# pineapple_2_2013_model_0.net
KiCad netlist of a schematic drawn in EAGLE
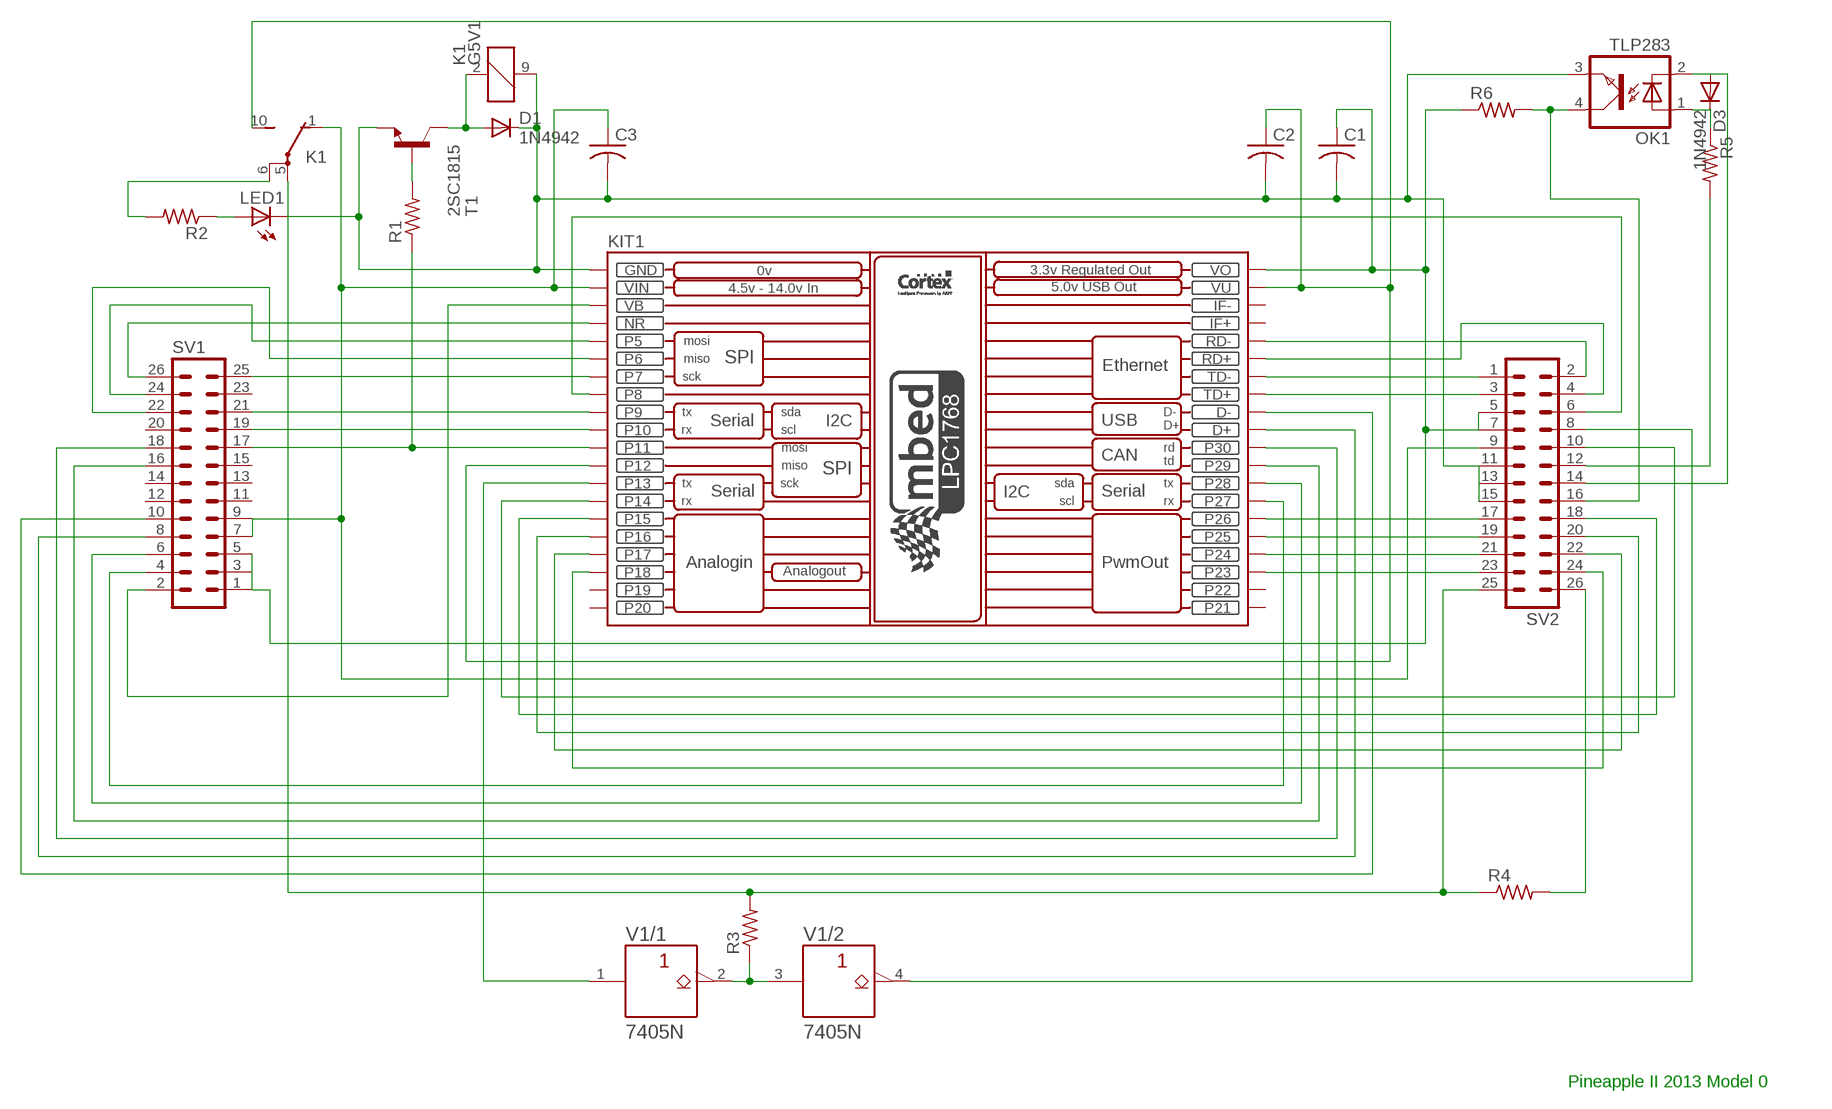
[diagram p0: schematic, sheet 1]

(export (version "E")
  (design (tool "Eeschema 10.0.6"))
  (components
    (comp (ref "C1")
      (value "C-US025-024X044")
      (footprint "eagle-import:C025-024X044")
      (libsource (lib "eagle-import") (part "C-US025-024X044"))
    )
    (comp (ref "C2")
      (value "C-US025-024X044")
      (footprint "eagle-import:C025-024X044")
      (libsource (lib "eagle-import") (part "C-US025-024X044"))
    )
    (comp (ref "C3")
      (value "C-US050-024X044")
      (footprint "eagle-import:C050-024X044")
      (libsource (lib "eagle-import") (part "C-US050-024X044"))
    )
    (comp (ref "D1")
      (value "1N4942")
      (footprint "eagle-import:DO41-10")
      (libsource (lib "eagle-import") (part "1N4942"))
    )
    (comp (ref "D3")
      (value "1N4942")
      (footprint "eagle-import:DO41-10")
      (libsource (lib "eagle-import") (part "1N4942"))
    )
    (comp (ref "K1")
      (value "G5V1")
      (footprint "eagle-import:G5V1")
      (fields (field (name "MPN") "G5V-1-DC24"))
      (libsource (lib "eagle-import") (part "G5V1"))
    )
    (comp (ref "KIT1")
      (value "MBED_NXP_LPC1768")
      (footprint "eagle-import:MBED-KIT")
      (libsource (lib "eagle-import") (part "MBED_NXP_LPC1768"))
    )
    (comp (ref "LED1")
      (value "LED3MM")
      (footprint "eagle-import:LED3MM")
      (libsource (lib "eagle-import") (part "LED3MM"))
    )
    (comp (ref "OK1")
      (value "TLP283")
      (footprint "eagle-import:MINI-FLAT-4")
      (libsource (lib "eagle-import") (part "TLP283"))
    )
    (comp (ref "R1")
      (value "R-US_0204/5")
      (footprint "eagle-import:0204_5")
      (libsource (lib "eagle-import") (part "R-US_0204/5"))
    )
    (comp (ref "R2")
      (value "R-US_0204/5")
      (footprint "eagle-import:0204_5")
      (libsource (lib "eagle-import") (part "R-US_0204/5"))
    )
    (comp (ref "R3")
      (value "R-US_0204/5")
      (footprint "eagle-import:0204_5")
      (libsource (lib "eagle-import") (part "R-US_0204/5"))
    )
    (comp (ref "R4")
      (value "R-US_0204/5")
      (footprint "eagle-import:0204_5")
      (libsource (lib "eagle-import") (part "R-US_0204/5"))
    )
    (comp (ref "R5")
      (value "R-US_0204/5")
      (footprint "eagle-import:0204_5")
      (libsource (lib "eagle-import") (part "R-US_0204/5"))
    )
    (comp (ref "R6")
      (value "R-US_0204/5")
      (footprint "eagle-import:0204_5")
      (libsource (lib "eagle-import") (part "R-US_0204/5"))
    )
    (comp (ref "SV1")
      (value "ML26L")
      (footprint "eagle-import:ML26L")
      (libsource (lib "eagle-import") (part "ML26L"))
    )
    (comp (ref "SV2")
      (value "ML26L")
      (footprint "eagle-import:ML26L")
      (libsource (lib "eagle-import") (part "ML26L"))
    )
    (comp (ref "T1")
      (value "2SC1815")
      (footprint "eagle-import:TO92-ECB")
      (libsource (lib "eagle-import") (part "2SC1815"))
    )
    (comp (ref "V1")
      (value "7405N")
      (footprint "eagle-import:DIL14")
      (libsource (lib "eagle-import") (part "7405N"))
    )
  )
  (nets
    (net (code "1") (name "Net-(K1A-1)") (class "Default")
      (node (ref "D1") (pin "A") (pinfunction "A_A") (pintype "passive"))
      (node (ref "K1") (pin "2") (pinfunction "1_2") (pintype "passive"))
      (node (ref "T1") (pin "C") (pinfunction "C_C") (pintype "passive"))
    )
    (net (code "2") (name "Net-(K1A-2)") (class "Default")
      (node (ref "C1") (pin "2") (pinfunction "2_2") (pintype "passive"))
      (node (ref "C2") (pin "2") (pinfunction "2_2") (pintype "passive"))
      (node (ref "C3") (pin "2") (pinfunction "2_2") (pintype "passive"))
      (node (ref "D1") (pin "C") (pinfunction "C_C") (pintype "passive"))
      (node (ref "K1") (pin "9") (pinfunction "2_9") (pintype "passive"))
      (node (ref "KIT1") (pin "GND") (pinfunction "GND_GND") (pintype "power_in"))
      (node (ref "LED1") (pin "K") (pinfunction "C_K") (pintype "passive"))
      (node (ref "OK1") (pin "3") (pinfunction "EMIT_3") (pintype "passive"))
      (node (ref "SV2") (pin "11") (pinfunction "11_11") (pintype "passive"))
      (node (ref "SV2") (pin "13") (pinfunction "13_13") (pintype "passive"))
      (node (ref "SV2") (pin "15") (pinfunction "15_15") (pintype "passive"))
      (node (ref "T1") (pin "E") (pinfunction "E_E") (pintype "passive"))
    )
    (net (code "3") (name "Net-(K1B-O)") (class "Default")
      (node (ref "C3") (pin "1") (pinfunction "1_1") (pintype "passive"))
      (node (ref "K1") (pin "1") (pinfunction "O_1") (pintype "passive"))
      (node (ref "KIT1") (pin "VIN") (pinfunction "VIN_VIN") (pintype "power_in"))
      (node (ref "SV1") (pin "7") (pinfunction "7_7") (pintype "passive"))
      (node (ref "SV1") (pin "9") (pinfunction "9_9") (pintype "passive"))
      (node (ref "SV2") (pin "9") (pinfunction "9_9") (pintype "passive"))
    )
    (net (code "4") (name "Net-(K1B-P-Pad5)") (class "Default")
      (node (ref "K1") (pin "5") (pinfunction "P_5") (pintype "passive"))
      (node (ref "R3") (pin "2") (pinfunction "2_2") (pintype "passive"))
      (node (ref "R4") (pin "1") (pinfunction "1_1") (pintype "passive"))
      (node (ref "SV2") (pin "25") (pinfunction "25_25") (pintype "passive"))
    )
    (net (code "5") (name "Net-(K1B-P-Pad6)") (class "Default")
      (node (ref "K1") (pin "6") (pinfunction "P_6") (pintype "passive"))
      (node (ref "R2") (pin "2") (pinfunction "2_2") (pintype "passive"))
    )
    (net (code "6") (name "Net-(K1B-S)") (class "Default")
      (node (ref "C2") (pin "1") (pinfunction "1_1") (pintype "passive"))
      (node (ref "K1") (pin "10") (pinfunction "S_10") (pintype "passive"))
      (node (ref "KIT1") (pin "P$12") (pinfunction "P12_P$12") (pintype "bidirectional"))
      (node (ref "KIT1") (pin "VU") (pinfunction "VU_VU") (pintype "power_in"))
    )
    (net (code "7") (name "Net-(KIT1-P5)") (class "Default")
      (node (ref "KIT1") (pin "P$5") (pinfunction "P5_P$5") (pintype "bidirectional"))
      (node (ref "SV1") (pin "24") (pinfunction "24_24") (pintype "passive"))
    )
    (net (code "8") (name "Net-(KIT1-P6)") (class "Default")
      (node (ref "KIT1") (pin "P$6") (pinfunction "P6_P$6") (pintype "bidirectional"))
      (node (ref "SV1") (pin "22") (pinfunction "22_22") (pintype "passive"))
    )
    (net (code "9") (name "Net-(KIT1-P7)") (class "Default")
      (node (ref "KIT1") (pin "P$7") (pinfunction "P7_P$7") (pintype "bidirectional"))
      (node (ref "SV1") (pin "25") (pinfunction "25_25") (pintype "passive"))
    )
    (net (code "10") (name "Net-(KIT1-P8)") (class "Default")
      (node (ref "KIT1") (pin "P$8") (pinfunction "P8_P$8") (pintype "bidirectional"))
      (node (ref "SV2") (pin "6") (pinfunction "6_6") (pintype "passive"))
    )
    (net (code "11") (name "Net-(KIT1-P9)") (class "Default")
      (node (ref "KIT1") (pin "P$9") (pinfunction "P9_P$9") (pintype "bidirectional"))
      (node (ref "SV1") (pin "21") (pinfunction "21_21") (pintype "passive"))
    )
    (net (code "12") (name "Net-(KIT1-P10)") (class "Default")
      (node (ref "KIT1") (pin "P$10") (pinfunction "P10_P$10") (pintype "bidirectional"))
      (node (ref "SV1") (pin "19") (pinfunction "19_19") (pintype "passive"))
    )
    (net (code "13") (name "Net-(KIT1-P11)") (class "Default")
      (node (ref "KIT1") (pin "P$11") (pinfunction "P11_P$11") (pintype "bidirectional"))
      (node (ref "R1") (pin "1") (pinfunction "1_1") (pintype "passive"))
      (node (ref "SV1") (pin "17") (pinfunction "17_17") (pintype "passive"))
    )
    (net (code "14") (name "Net-(KIT1-P13)") (class "Default")
      (node (ref "KIT1") (pin "P$13") (pinfunction "P13_P$13") (pintype "bidirectional"))
      (node (ref "V1") (pin "1") (pinfunction "A_1") (pintype "input"))
    )
    (net (code "15") (name "Net-(KIT1-P14)") (class "Default")
      (node (ref "KIT1") (pin "P$14") (pinfunction "P14_P$14") (pintype "bidirectional"))
      (node (ref "SV2") (pin "10") (pinfunction "10_10") (pintype "passive"))
    )
    (net (code "16") (name "Net-(KIT1-P15)") (class "Default")
      (node (ref "KIT1") (pin "P$15") (pinfunction "P15_P$15") (pintype "bidirectional"))
      (node (ref "SV2") (pin "18") (pinfunction "18_18") (pintype "passive"))
    )
    (net (code "17") (name "Net-(KIT1-P16)") (class "Default")
      (node (ref "KIT1") (pin "P$16") (pinfunction "P16_P$16") (pintype "bidirectional"))
      (node (ref "SV2") (pin "20") (pinfunction "20_20") (pintype "passive"))
    )
    (net (code "18") (name "Net-(KIT1-P17)") (class "Default")
      (node (ref "KIT1") (pin "P$17") (pinfunction "P17_P$17") (pintype "bidirectional"))
      (node (ref "SV2") (pin "22") (pinfunction "22_22") (pintype "passive"))
    )
    (net (code "19") (name "Net-(KIT1-P18)") (class "Default")
      (node (ref "KIT1") (pin "P$18") (pinfunction "P18_P$18") (pintype "bidirectional"))
      (node (ref "SV2") (pin "24") (pinfunction "24_24") (pintype "passive"))
    )
    (net (code "20") (name "Net-(KIT1-P23)") (class "Default")
      (node (ref "KIT1") (pin "P$23") (pinfunction "P23_P$23") (pintype "bidirectional"))
      (node (ref "SV2") (pin "23") (pinfunction "23_23") (pintype "passive"))
    )
    (net (code "21") (name "Net-(KIT1-P24)") (class "Default")
      (node (ref "KIT1") (pin "P$24") (pinfunction "P24_P$24") (pintype "bidirectional"))
      (node (ref "SV2") (pin "21") (pinfunction "21_21") (pintype "passive"))
    )
    (net (code "22") (name "Net-(KIT1-P25)") (class "Default")
      (node (ref "KIT1") (pin "P$25") (pinfunction "P25_P$25") (pintype "bidirectional"))
      (node (ref "SV2") (pin "19") (pinfunction "19_19") (pintype "passive"))
    )
    (net (code "23") (name "Net-(KIT1-P26)") (class "Default")
      (node (ref "KIT1") (pin "P$26") (pinfunction "P26_P$26") (pintype "bidirectional"))
      (node (ref "SV2") (pin "17") (pinfunction "17_17") (pintype "passive"))
    )
    (net (code "24") (name "Net-(KIT1-P27)") (class "Default")
      (node (ref "KIT1") (pin "P$27") (pinfunction "P27_P$27") (pintype "bidirectional"))
      (node (ref "SV1") (pin "4") (pinfunction "4_4") (pintype "passive"))
    )
    (net (code "25") (name "Net-(KIT1-P28)") (class "Default")
      (node (ref "KIT1") (pin "P$28") (pinfunction "P28_P$28") (pintype "bidirectional"))
      (node (ref "SV1") (pin "6") (pinfunction "6_6") (pintype "passive"))
    )
    (net (code "26") (name "Net-(KIT1-P29)") (class "Default")
      (node (ref "KIT1") (pin "P$29") (pinfunction "P29_P$29") (pintype "bidirectional"))
      (node (ref "SV1") (pin "16") (pinfunction "16_16") (pintype "passive"))
    )
    (net (code "27") (name "Net-(KIT1-P30)") (class "Default")
      (node (ref "KIT1") (pin "P$30") (pinfunction "P30_P$30") (pintype "bidirectional"))
      (node (ref "SV1") (pin "18") (pinfunction "18_18") (pintype "passive"))
    )
    (net (code "28") (name "Net-(KIT1-PadD+)") (class "Default")
      (node (ref "KIT1") (pin "D+") (pinfunction "D+_D+") (pintype "bidirectional"))
      (node (ref "SV1") (pin "8") (pinfunction "8_8") (pintype "passive"))
    )
    (net (code "29") (name "Net-(KIT1-PadD-)") (class "Default")
      (node (ref "KIT1") (pin "D-") (pinfunction "D-_D-") (pintype "bidirectional"))
      (node (ref "SV1") (pin "10") (pinfunction "10_10") (pintype "passive"))
    )
    (net (code "30") (name "Net-(KIT1-PadNR)") (class "Default")
      (node (ref "KIT1") (pin "NR") (pinfunction "NR_NR") (pintype "power_in"))
      (node (ref "SV1") (pin "26") (pinfunction "26_26") (pintype "passive"))
    )
    (net (code "31") (name "Net-(KIT1-PadRD+)") (class "Default")
      (node (ref "KIT1") (pin "RD+") (pinfunction "RD+_RD+") (pintype "bidirectional"))
      (node (ref "SV2") (pin "4") (pinfunction "4_4") (pintype "passive"))
    )
    (net (code "32") (name "Net-(KIT1-PadRD-)") (class "Default")
      (node (ref "KIT1") (pin "RD-") (pinfunction "RD-_RD-") (pintype "bidirectional"))
      (node (ref "SV2") (pin "2") (pinfunction "2_2") (pintype "passive"))
    )
    (net (code "33") (name "Net-(KIT1-PadTD+)") (class "Default")
      (node (ref "KIT1") (pin "TD+") (pinfunction "TD+_TD+") (pintype "bidirectional"))
      (node (ref "SV2") (pin "3") (pinfunction "3_3") (pintype "passive"))
    )
    (net (code "34") (name "Net-(KIT1-PadTD-)") (class "Default")
      (node (ref "KIT1") (pin "TD-") (pinfunction "TD-_TD-") (pintype "bidirectional"))
      (node (ref "SV2") (pin "1") (pinfunction "1_1") (pintype "passive"))
    )
    (net (code "35") (name "Net-(KIT1-PadVB)") (class "Default")
      (node (ref "KIT1") (pin "VB") (pinfunction "VB_VB") (pintype "power_in"))
      (node (ref "SV1") (pin "2") (pinfunction "2_2") (pintype "passive"))
    )
    (net (code "36") (name "Net-(KIT1-VO)") (class "Default")
      (node (ref "C1") (pin "1") (pinfunction "1_1") (pintype "passive"))
      (node (ref "KIT1") (pin "VOUT") (pinfunction "VO_VOUT") (pintype "power_in"))
      (node (ref "R6") (pin "1") (pinfunction "1_1") (pintype "passive"))
      (node (ref "SV1") (pin "1") (pinfunction "1_1") (pintype "passive"))
      (node (ref "SV1") (pin "3") (pinfunction "3_3") (pintype "passive"))
      (node (ref "SV1") (pin "5") (pinfunction "5_5") (pintype "passive"))
      (node (ref "SV2") (pin "5") (pinfunction "5_5") (pintype "passive"))
      (node (ref "SV2") (pin "7") (pinfunction "7_7") (pintype "passive"))
    )
    (net (code "37") (name "Net-(LED1-PadA)") (class "Default")
      (node (ref "LED1") (pin "A") (pinfunction "A_A") (pintype "passive"))
      (node (ref "R2") (pin "1") (pinfunction "1_1") (pintype "passive"))
    )
    (net (code "38") (name "Net-(OK1-A)") (class "Default")
      (node (ref "D3") (pin "C") (pinfunction "C_C") (pintype "passive"))
      (node (ref "OK1") (pin "1") (pinfunction "A_1") (pintype "passive"))
      (node (ref "R5") (pin "1") (pinfunction "1_1") (pintype "passive"))
    )
    (net (code "39") (name "Net-(OK1-C)") (class "Default")
      (node (ref "D3") (pin "A") (pinfunction "A_A") (pintype "passive"))
      (node (ref "OK1") (pin "2") (pinfunction "C_2") (pintype "passive"))
      (node (ref "SV2") (pin "14") (pinfunction "14_14") (pintype "passive"))
    )
    (net (code "40") (name "Net-(OK1-COL)") (class "Default")
      (node (ref "OK1") (pin "4") (pinfunction "COL_4") (pintype "passive"))
      (node (ref "R6") (pin "2") (pinfunction "2_2") (pintype "passive"))
      (node (ref "SV2") (pin "16") (pinfunction "16_16") (pintype "passive"))
    )
    (net (code "41") (name "Net-(R1-Pad2)") (class "Default")
      (node (ref "R1") (pin "2") (pinfunction "2_2") (pintype "passive"))
      (node (ref "T1") (pin "B") (pinfunction "B_B") (pintype "passive"))
    )
    (net (code "42") (name "Net-(R4-Pad2)") (class "Default")
      (node (ref "R4") (pin "2") (pinfunction "2_2") (pintype "passive"))
      (node (ref "SV2") (pin "26") (pinfunction "26_26") (pintype "passive"))
    )
    (net (code "43") (name "Net-(R5-Pad2)") (class "Default")
      (node (ref "R5") (pin "2") (pinfunction "2_2") (pintype "passive"))
      (node (ref "SV2") (pin "12") (pinfunction "12_12") (pintype "passive"))
    )
    (net (code "44") (name "Net-(V1C-Y)") (class "Default")
      (node (ref "R3") (pin "1") (pinfunction "1_1") (pintype "passive"))
      (node (ref "V1") (pin "2") (pinfunction "Y_2") (pintype "open_collector"))
      (node (ref "V1") (pin "3") (pinfunction "A_3") (pintype "input"))
    )
    (net (code "45") (name "Net-(V1D-Y)") (class "Default")
      (node (ref "SV2") (pin "8") (pinfunction "8_8") (pintype "passive"))
      (node (ref "V1") (pin "4") (pinfunction "Y_4") (pintype "open_collector"))
    )
    (net (code "46") (name "unconnected-(KIT1-P19-PadP$19)") (class "Default")
      (node (ref "KIT1") (pin "P$19") (pinfunction "P19_P$19") (pintype "bidirectional"))
    )
    (net (code "47") (name "unconnected-(KIT1-P20-PadP$20)") (class "Default")
      (node (ref "KIT1") (pin "P$20") (pinfunction "P20_P$20") (pintype "bidirectional"))
    )
    (net (code "48") (name "unconnected-(KIT1-P21-PadP$21)") (class "Default")
      (node (ref "KIT1") (pin "P$21") (pinfunction "P21_P$21") (pintype "bidirectional"))
    )
    (net (code "49") (name "unconnected-(KIT1-P22-PadP$22)") (class "Default")
      (node (ref "KIT1") (pin "P$22") (pinfunction "P22_P$22") (pintype "bidirectional"))
    )
    (net (code "50") (name "unconnected-(KIT1-PadIF+)") (class "Default")
      (node (ref "KIT1") (pin "IF+") (pinfunction "IF+_IF+") (pintype "bidirectional"))
    )
    (net (code "51") (name "unconnected-(KIT1-PadIF-)") (class "Default")
      (node (ref "KIT1") (pin "IF-") (pinfunction "IF-_IF-") (pintype "bidirectional"))
    )
    (net (code "52") (name "unconnected-(SV1-Pad11)") (class "Default")
      (node (ref "SV1") (pin "11") (pinfunction "11_11") (pintype "passive"))
    )
    (net (code "53") (name "unconnected-(SV1-Pad12)") (class "Default")
      (node (ref "SV1") (pin "12") (pinfunction "12_12") (pintype "passive"))
    )
    (net (code "54") (name "unconnected-(SV1-Pad13)") (class "Default")
      (node (ref "SV1") (pin "13") (pinfunction "13_13") (pintype "passive"))
    )
    (net (code "55") (name "unconnected-(SV1-Pad14)") (class "Default")
      (node (ref "SV1") (pin "14") (pinfunction "14_14") (pintype "passive"))
    )
    (net (code "56") (name "unconnected-(SV1-Pad15)") (class "Default")
      (node (ref "SV1") (pin "15") (pinfunction "15_15") (pintype "passive"))
    )
    (net (code "57") (name "unconnected-(SV1-Pad20)") (class "Default")
      (node (ref "SV1") (pin "20") (pinfunction "20_20") (pintype "passive"))
    )
    (net (code "58") (name "unconnected-(SV1-Pad23)") (class "Default")
      (node (ref "SV1") (pin "23") (pinfunction "23_23") (pintype "passive"))
    )
  )
)
